# LEDdriver-LM3409_-_Strobe.net
KiCad netlist of a schematic drawn in Altium Designer
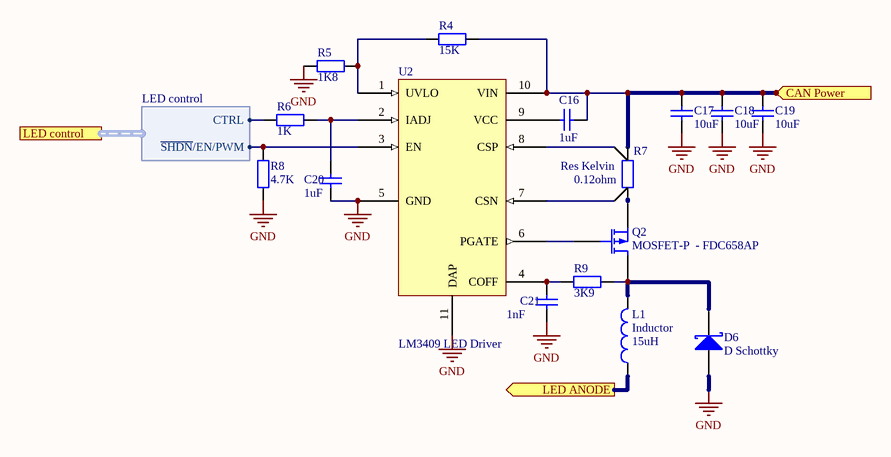
[diagram p0: LEDdriver-LM3409 - Strobe.SchDoc]

(export (version "E")
  (design (tool "Eeschema 10.0.6"))
  (components
    (comp (ref "C16")
      (value "1uF")
      (footprint "C0603")
      (description "Capacitor")
      (fields (field (name "Comment") "Cap") (field (name "PUBLISHER") "Altium Limited"))
      (libsource (lib "Miscellaneous Devices") (part "Cap"))
    )
    (comp (ref "C17")
      (value "10uF")
      (footprint "Capacitor 1210 (3225) package")
      (description "Capacitor")
      (fields (field (name "Comment") "Cap") (field (name "PUBLISHER") "Altium Limited"))
      (libsource (lib "Miscellaneous Devices") (part "Cap"))
    )
    (comp (ref "C18")
      (value "10uF")
      (footprint "Capacitor 1210 (3225) package")
      (description "Capacitor")
      (fields (field (name "Comment") "Cap") (field (name "PUBLISHER") "Altium Limited"))
      (libsource (lib "Miscellaneous Devices") (part "Cap"))
    )
    (comp (ref "C19")
      (value "10uF")
      (footprint "Capacitor 1210 (3225) package")
      (description "Capacitor")
      (fields (field (name "Comment") "Cap") (field (name "PUBLISHER") "Altium Limited"))
      (libsource (lib "Miscellaneous Devices") (part "Cap"))
    )
    (comp (ref "C20")
      (value "1uF")
      (footprint "C0603")
      (description "Capacitor")
      (fields (field (name "Comment") "Cap") (field (name "PUBLISHER") "Altium Limited"))
      (libsource (lib "Miscellaneous Devices") (part "Cap"))
    )
    (comp (ref "C21")
      (value "1nF")
      (footprint "C0603")
      (description "Capacitor")
      (fields (field (name "Comment") "Cap") (field (name "PUBLISHER") "Altium Limited"))
      (libsource (lib "Miscellaneous Devices") (part "Cap"))
    )
    (comp (ref "D6")
      (value "D Schottky")
      (footprint "Schottky rectifier")
      (description "Schottky Diode")
      (fields (field (name "PUBLISHER") "Altium Limited"))
      (libsource (lib "Miscellaneous Devices") (part "D Schottky"))
    )
    (comp (ref "L1")
      (value "Inductor")
      (footprint "Inductor 3131")
      (fields (field (name "ALTIUM_VALUE") "15uH") (field (name "PUBLISHER") "Altium Limited"))
      (libsource (lib "Miscellaneous Devices") (part "Inductor"))
    )
    (comp (ref "Q2")
      (value "MOSFET-P  - FDC658AP")
      (footprint "SuperSOT6 - FDC658AP")
      (description "P-Channel MOSFET")
      (fields (field (name "PUBLISHER") "Altium Limited"))
      (libsource (lib "Miscellaneous Devices") (part "MOSFET-P"))
    )
    (comp (ref "R4")
      (value "15K")
      (footprint "R0603")
      (description "Resistor")
      (fields (field (name "Comment") "Res"))
      (libsource (lib "Miscellaneous Devices") (part "Res2"))
    )
    (comp (ref "R5")
      (value "1K8")
      (footprint "R0603")
      (description "Resistor")
      (fields (field (name "Comment") "Res"))
      (libsource (lib "Miscellaneous Devices") (part "Res2"))
    )
    (comp (ref "R6")
      (value "1K")
      (footprint "R0603")
      (description "Resistor")
      (fields (field (name "Comment") "Res"))
      (libsource (lib "Miscellaneous Devices") (part "Res2"))
    )
    (comp (ref "R7")
      (value "Res Kelvin")
      (footprint "2512 package + Kelvin Cons - ERJ1TR Rsns")
      (description "Resistor Kelvin")
      (fields (field (name "ALTIUM_VALUE") "0.12ohm") (field (name "PUBLISHER") "Altium Limited"))
      (libsource (lib "resistor-kelvin") (part "Res Kelvin"))
    )
    (comp (ref "R8")
      (value "4.7K")
      (footprint "R0603")
      (description "Resistor")
      (fields (field (name "Comment") "Res"))
      (libsource (lib "") (part "Res2_1"))
    )
    (comp (ref "R9")
      (value "3K9")
      (footprint "R0603")
      (description "Resistor")
      (fields (field (name "Comment") "Res"))
      (libsource (lib "Miscellaneous Devices") (part "Res2"))
    )
    (comp (ref "U2")
      (value "LM3409 LED Driver")
      (footprint "10eMSOP + thermal pad - LM3409")
      (description "PFET Buck Controller for High Power LED Drivers")
      (libsource (lib "LM3409") (part "LM3409"))
    )
  )
  (nets
    (net (code "3") (name "/CAN Power") (class "Default")
      (node (ref "C16") (pin "1") (pinfunction "1_1") (pintype "passive"))
      (node (ref "C17") (pin "1") (pinfunction "1_1") (pintype "passive"))
      (node (ref "C18") (pin "1") (pinfunction "1_1") (pintype "passive"))
      (node (ref "C19") (pin "1") (pinfunction "1_1") (pintype "passive"))
      (node (ref "R4") (pin "1") (pinfunction "1_1") (pintype "passive"))
      (node (ref "R7") (pin "2") (pinfunction "2_2") (pintype "passive"))
      (node (ref "U2") (pin "10") (pinfunction "VIN_10") (pintype "passive"))
    )
    (net (code "4") (name "/CTRL") (class "Default")
      (node (ref "R6") (pin "2") (pinfunction "2_2") (pintype "passive"))
    )
    (net (code "5") (name "/LED ANODE") (class "Default")
      (node (ref "L1") (pin "1") (pinfunction "1_1") (pintype "passive"))
    )
    (net (code "7") (name "/~{SHDN}{slash}EN{slash}PWM") (class "Default")
      (node (ref "R8") (pin "2") (pinfunction "2_2") (pintype "passive"))
      (node (ref "U2") (pin "3") (pinfunction "EN_3") (pintype "input"))
    )
    (net (code "8") (name "GND") (class "Default")
      (node (ref "C17") (pin "2") (pinfunction "2_2") (pintype "passive"))
      (node (ref "C18") (pin "2") (pinfunction "2_2") (pintype "passive"))
      (node (ref "C19") (pin "2") (pinfunction "2_2") (pintype "passive"))
      (node (ref "C20") (pin "2") (pinfunction "2_2") (pintype "passive"))
      (node (ref "C21") (pin "2") (pinfunction "2_2") (pintype "passive"))
      (node (ref "D6") (pin "1") (pinfunction "A_1") (pintype "passive"))
      (node (ref "R5") (pin "2") (pinfunction "2_2") (pintype "passive"))
      (node (ref "R8") (pin "1") (pinfunction "1_1") (pintype "passive"))
      (node (ref "U2") (pin "11") (pinfunction "DAP_11") (pintype "power_in"))
      (node (ref "U2") (pin "5") (pinfunction "GND_5") (pintype "power_in"))
    )
    (net (code "9") (name "Net-(D6-K)") (class "Default")
      (node (ref "D6") (pin "2") (pinfunction "K_2") (pintype "passive"))
      (node (ref "L1") (pin "2") (pinfunction "2_2") (pintype "passive"))
      (node (ref "Q2") (pin "1") (pinfunction "D_1") (pintype "passive"))
      (node (ref "R9") (pin "1") (pinfunction "1_1") (pintype "passive"))
    )
    (net (code "10") (name "Net-(Q2-G)") (class "Default")
      (node (ref "Q2") (pin "2") (pinfunction "G_2") (pintype "passive"))
      (node (ref "U2") (pin "6") (pinfunction "PGATE_6") (pintype "output"))
    )
    (net (code "11") (name "Net-(Q2-S)") (class "Default")
      (node (ref "Q2") (pin "3") (pinfunction "S_3") (pintype "passive"))
      (node (ref "R7") (pin "1") (pinfunction "1_1") (pintype "passive"))
    )
    (net (code "12") (name "Net-(U2-COFF)") (class "Default")
      (node (ref "C21") (pin "1") (pinfunction "1_1") (pintype "passive"))
      (node (ref "R9") (pin "2") (pinfunction "2_2") (pintype "passive"))
      (node (ref "U2") (pin "4") (pinfunction "COFF_4") (pintype "passive"))
    )
    (net (code "13") (name "Net-(U2-CSN)") (class "Default")
      (node (ref "R7") (pin "3") (pinfunction "3_3") (pintype "power_in"))
      (node (ref "U2") (pin "7") (pinfunction "CSN_7") (pintype "input"))
    )
    (net (code "14") (name "Net-(U2-CSP)") (class "Default")
      (node (ref "R7") (pin "4") (pinfunction "4_4") (pintype "power_in"))
      (node (ref "U2") (pin "8") (pinfunction "CSP_8") (pintype "input"))
    )
    (net (code "15") (name "Net-(U2-IADJ)") (class "Default")
      (node (ref "C20") (pin "1") (pinfunction "1_1") (pintype "passive"))
      (node (ref "R6") (pin "1") (pinfunction "1_1") (pintype "passive"))
      (node (ref "U2") (pin "2") (pinfunction "IADJ_2") (pintype "input"))
    )
    (net (code "16") (name "Net-(U2-UVLO)") (class "Default")
      (node (ref "R4") (pin "2") (pinfunction "2_2") (pintype "passive"))
      (node (ref "R5") (pin "1") (pinfunction "1_1") (pintype "passive"))
      (node (ref "U2") (pin "1") (pinfunction "UVLO_1") (pintype "input"))
    )
    (net (code "17") (name "Net-(U2-VCC)") (class "Default")
      (node (ref "C16") (pin "2") (pinfunction "2_2") (pintype "passive"))
      (node (ref "U2") (pin "9") (pinfunction "VCC_9") (pintype "power_in"))
    )
  )
)
